# WHEEL-MOTORs.net
KiCad netlist of a schematic drawn in Altium Designer
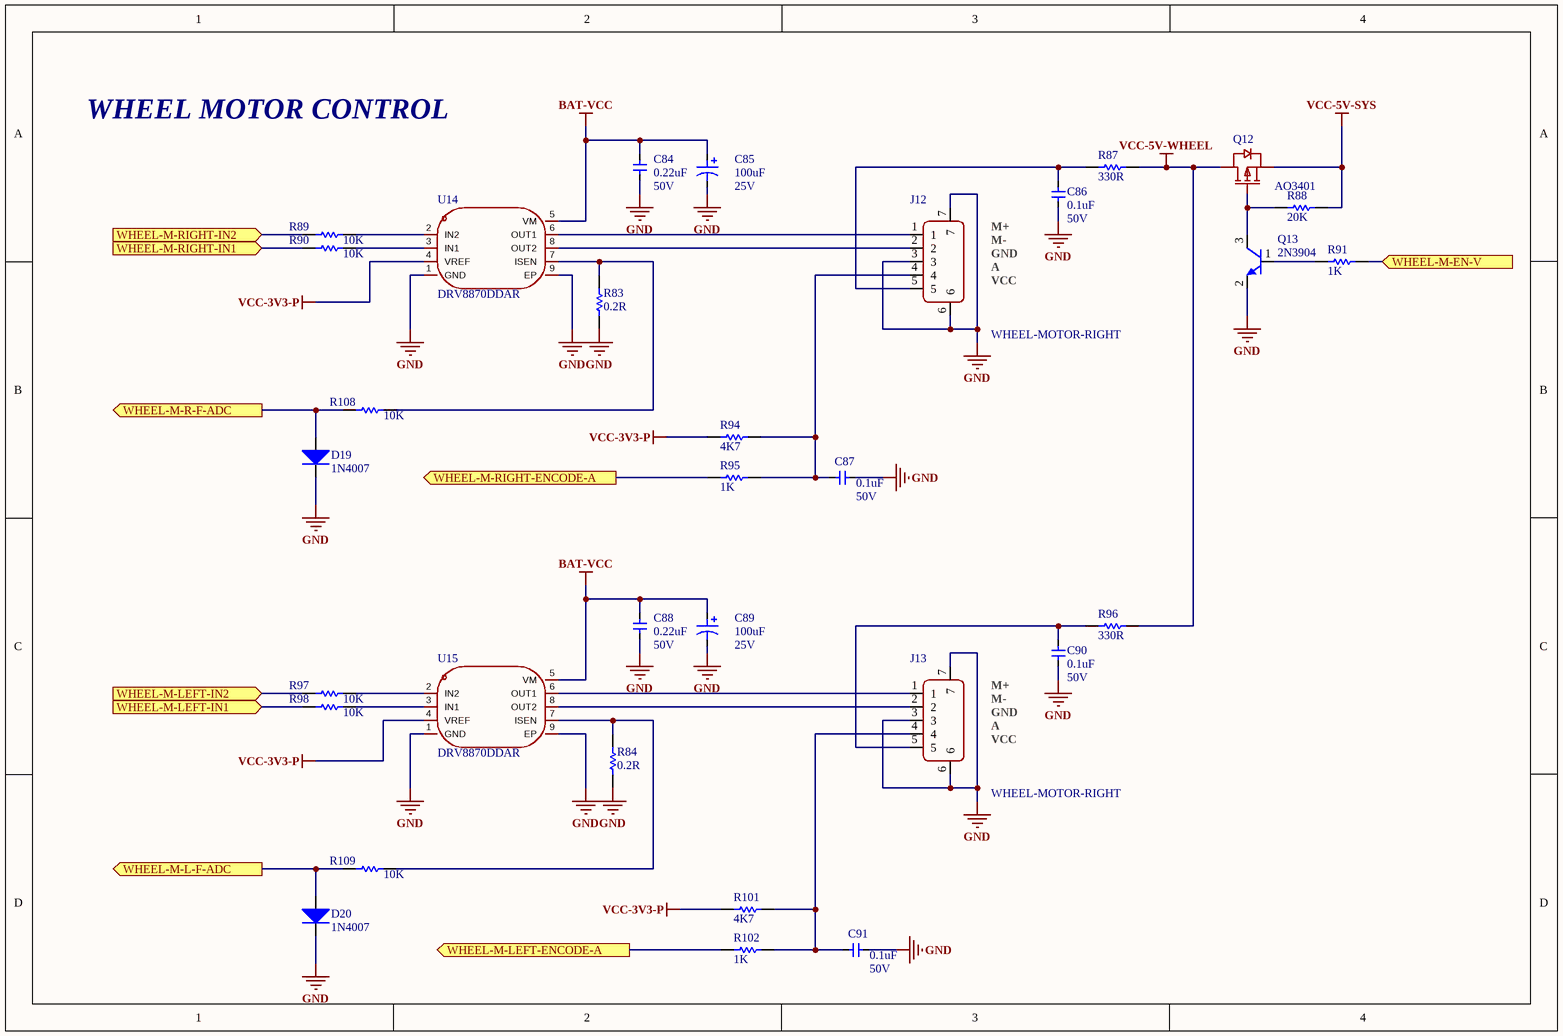
[diagram p0: WHEEL-MOTORs .SchDoc]

(export (version "E")
  (design (tool "Eeschema 10.0.6"))
  (components
    (comp (ref "C84")
      (value "0.22uF")
      (footprint "CAP-0402")
      (fields (field (name "VOLTAGERATE") "50V"))
      (libsource (lib "DesignLibrary") (part "Capacitor-1"))
    )
    (comp (ref "C85")
      (value "100uF")
      (footprint "CAP-SMD_BD6.3-L6.6-W6.6-FD")
      (fields (field (name "VOLTAGERATE") "25V"))
      (libsource (lib "DesignLibrary") (part "Capacitor-2"))
    )
    (comp (ref "C86")
      (value "0.1uF")
      (footprint "CAP-0402")
      (fields (field (name "VOLTAGERATE") "50V"))
      (libsource (lib "DesignLibrary") (part "Capacitor-1"))
    )
    (comp (ref "C87")
      (value "0.1uF")
      (footprint "CAP-0402")
      (fields (field (name "VOLTAGERATE") "50V"))
      (libsource (lib "DesignLibrary") (part "Capacitor-1"))
    )
    (comp (ref "C88")
      (value "0.22uF")
      (footprint "CAP-0402")
      (fields (field (name "VOLTAGERATE") "50V"))
      (libsource (lib "DesignLibrary") (part "Capacitor-1"))
    )
    (comp (ref "C89")
      (value "100uF")
      (footprint "CAP-SMD_BD6.3-L6.6-W6.6-FD")
      (fields (field (name "VOLTAGERATE") "25V"))
      (libsource (lib "DesignLibrary") (part "Capacitor-2"))
    )
    (comp (ref "C90")
      (value "0.1uF")
      (footprint "CAP-0402")
      (fields (field (name "VOLTAGERATE") "50V"))
      (libsource (lib "DesignLibrary") (part "Capacitor-1"))
    )
    (comp (ref "C91")
      (value "0.1uF")
      (footprint "CAP-0402")
      (fields (field (name "VOLTAGERATE") "50V"))
      (libsource (lib "DesignLibrary") (part "Capacitor-1"))
    )
    (comp (ref "D19")
      (value "1N4007")
      (footprint "SOD123")
      (libsource (lib "DesignLibrary") (part "DIODE-1"))
    )
    (comp (ref "D20")
      (value "1N4007")
      (footprint "SOD123")
      (libsource (lib "DesignLibrary") (part "DIODE-1"))
    )
    (comp (ref "J12")
      (value "WHEEL-MOTOR-RIGHT")
      (footprint "CONN-SMD_5P-P1.50_ZX-ZH1.5-5PWT")
      (libsource (lib "DesignLibrary") (part "HDRx5"))
    )
    (comp (ref "J13")
      (value "WHEEL-MOTOR-RIGHT")
      (footprint "CONN-SMD_5P-P1.50_ZX-ZH1.5-5PWT")
      (libsource (lib "DesignLibrary") (part "HDRx5"))
    )
    (comp (ref "Q12")
      (value "AO3401")
      (footprint "SOT23-3D")
      (libsource (lib "DesignLibrary") (part "P-MOS-SOT23"))
    )
    (comp (ref "Q13")
      (value "2N3904")
      (footprint "SOT23-3D")
      (libsource (lib "DesignLibrary") (part "NPN-SOT23"))
    )
    (comp (ref "R83")
      (value "0.2R")
      (footprint "RES-0603")
      (libsource (lib "DesignLibrary") (part "Resistor-1"))
    )
    (comp (ref "R84")
      (value "0.2R")
      (footprint "RES-0603")
      (libsource (lib "DesignLibrary") (part "Resistor-1"))
    )
    (comp (ref "R87")
      (value "330R")
      (footprint "RES-0603")
      (libsource (lib "DesignLibrary") (part "Resistor-1"))
    )
    (comp (ref "R88")
      (value "20K")
      (footprint "RES-0402")
      (libsource (lib "DesignLibrary") (part "Resistor-1"))
    )
    (comp (ref "R89")
      (value "10K")
      (footprint "RES-0402")
      (libsource (lib "DesignLibrary") (part "Resistor-1"))
    )
    (comp (ref "R90")
      (value "10K")
      (footprint "RES-0402")
      (libsource (lib "DesignLibrary") (part "Resistor-1"))
    )
    (comp (ref "R91")
      (value "1K")
      (footprint "RES-0402")
      (libsource (lib "DesignLibrary") (part "Resistor-1"))
    )
    (comp (ref "R94")
      (value "4K7")
      (footprint "RES-0402")
      (libsource (lib "DesignLibrary") (part "Resistor-1"))
    )
    (comp (ref "R95")
      (value "1K")
      (footprint "RES-0402")
      (libsource (lib "DesignLibrary") (part "Resistor-1"))
    )
    (comp (ref "R96")
      (value "330R")
      (footprint "RES-0603")
      (libsource (lib "DesignLibrary") (part "Resistor-1"))
    )
    (comp (ref "R97")
      (value "10K")
      (footprint "RES-0402")
      (libsource (lib "DesignLibrary") (part "Resistor-1"))
    )
    (comp (ref "R98")
      (value "10K")
      (footprint "RES-0402")
      (libsource (lib "DesignLibrary") (part "Resistor-1"))
    )
    (comp (ref "R101")
      (value "4K7")
      (footprint "RES-0402")
      (libsource (lib "DesignLibrary") (part "Resistor-1"))
    )
    (comp (ref "R102")
      (value "1K")
      (footprint "RES-0402")
      (libsource (lib "DesignLibrary") (part "Resistor-1"))
    )
    (comp (ref "R108")
      (value "10K")
      (footprint "RES-0402")
      (libsource (lib "DesignLibrary") (part "Resistor-1"))
    )
    (comp (ref "R109")
      (value "10K")
      (footprint "RES-0402")
      (libsource (lib "DesignLibrary") (part "Resistor-1"))
    )
    (comp (ref "U14")
      (value "DRV8870DDAR")
      (footprint "HSOP-8_L5.0-W4.0-P1.27-LS6.2-BL-EP")
      (libsource (lib "DesignLibrary") (part "DRV8870"))
    )
    (comp (ref "U15")
      (value "DRV8870DDAR")
      (footprint "HSOP-8_L5.0-W4.0-P1.27-LS6.2-BL-EP")
      (libsource (lib "DesignLibrary") (part "DRV8870"))
    )
  )
  (nets
    (net (code "1") (name "/WHEEL-M-EN-V") (class "Default") (node (ref "R91") (pin "2") (pintype "passive")))
    (net (code "2") (name "/WHEEL-M-L-F-ADC") (class "Default")
      (node (ref "D20") (pin "1") (pinfunction "A_1") (pintype "passive"))
      (node (ref "R109") (pin "1") (pintype "passive"))
    )
    (net (code "3") (name "/WHEEL-M-LEFT-ENCODE-A") (class "Default")
      (node (ref "R102") (pin "1") (pintype "passive"))
    )
    (net (code "4") (name "/WHEEL-M-LEFT-IN1") (class "Default")
      (node (ref "R98") (pin "1") (pintype "passive"))
    )
    (net (code "5") (name "/WHEEL-M-LEFT-IN2") (class "Default")
      (node (ref "R97") (pin "1") (pintype "passive"))
    )
    (net (code "6") (name "/WHEEL-M-R-F-ADC") (class "Default")
      (node (ref "D19") (pin "1") (pinfunction "A_1") (pintype "passive"))
      (node (ref "R108") (pin "1") (pintype "passive"))
    )
    (net (code "7") (name "/WHEEL-M-RIGHT-ENCODE-A") (class "Default")
      (node (ref "R95") (pin "1") (pintype "passive"))
    )
    (net (code "8") (name "/WHEEL-M-RIGHT-IN1") (class "Default")
      (node (ref "R90") (pin "1") (pintype "passive"))
    )
    (net (code "9") (name "/WHEEL-M-RIGHT-IN2") (class "Default")
      (node (ref "R89") (pin "1") (pintype "passive"))
    )
    (net (code "10") (name "BAT-VCC") (class "Default")
      (node (ref "C84") (pin "2") (pinfunction "2_2") (pintype "passive"))
      (node (ref "C85") (pin "1") (pinfunction "1_1") (pintype "passive"))
      (node (ref "C88") (pin "2") (pinfunction "2_2") (pintype "passive"))
      (node (ref "C89") (pin "1") (pinfunction "1_1") (pintype "passive"))
      (node (ref "U14") (pin "5") (pinfunction "VM_5") (pintype "passive"))
      (node (ref "U15") (pin "5") (pinfunction "VM_5") (pintype "passive"))
    )
    (net (code "11") (name "GND") (class "Default")
      (node (ref "C84") (pin "1") (pinfunction "1_1") (pintype "passive"))
      (node (ref "C85") (pin "2") (pinfunction "2_2") (pintype "passive"))
      (node (ref "C86") (pin "2") (pinfunction "2_2") (pintype "passive"))
      (node (ref "C87") (pin "1") (pinfunction "1_1") (pintype "passive"))
      (node (ref "C88") (pin "1") (pinfunction "1_1") (pintype "passive"))
      (node (ref "C89") (pin "2") (pinfunction "2_2") (pintype "passive"))
      (node (ref "C90") (pin "2") (pinfunction "2_2") (pintype "passive"))
      (node (ref "C91") (pin "1") (pinfunction "1_1") (pintype "passive"))
      (node (ref "D19") (pin "2") (pinfunction "K_2") (pintype "passive"))
      (node (ref "D20") (pin "2") (pinfunction "K_2") (pintype "passive"))
      (node (ref "J12") (pin "3") (pinfunction "3_3") (pintype "passive"))
      (node (ref "J12") (pin "6") (pinfunction "6_6") (pintype "passive"))
      (node (ref "J12") (pin "7") (pinfunction "7_7") (pintype "passive"))
      (node (ref "J13") (pin "3") (pinfunction "3_3") (pintype "passive"))
      (node (ref "J13") (pin "6") (pinfunction "6_6") (pintype "passive"))
      (node (ref "J13") (pin "7") (pinfunction "7_7") (pintype "passive"))
      (node (ref "Q13") (pin "2") (pinfunction "E_2") (pintype "passive"))
      (node (ref "R83") (pin "1") (pintype "passive"))
      (node (ref "R84") (pin "1") (pintype "passive"))
      (node (ref "U14") (pin "1") (pinfunction "GND_1") (pintype "passive"))
      (node (ref "U14") (pin "9") (pinfunction "EP_9") (pintype "passive"))
      (node (ref "U15") (pin "1") (pinfunction "GND_1") (pintype "passive"))
      (node (ref "U15") (pin "9") (pinfunction "EP_9") (pintype "passive"))
    )
    (net (code "12") (name "Net-(C86-Pad1)") (class "Default")
      (node (ref "C86") (pin "1") (pinfunction "1_1") (pintype "passive"))
      (node (ref "J12") (pin "5") (pinfunction "5_5") (pintype "passive"))
      (node (ref "R87") (pin "1") (pintype "passive"))
    )
    (net (code "13") (name "Net-(C87-Pad2)") (class "Default")
      (node (ref "C87") (pin "2") (pinfunction "2_2") (pintype "passive"))
      (node (ref "J12") (pin "4") (pinfunction "4_4") (pintype "passive"))
      (node (ref "R94") (pin "2") (pintype "passive"))
      (node (ref "R95") (pin "2") (pintype "passive"))
    )
    (net (code "14") (name "Net-(C90-Pad1)") (class "Default")
      (node (ref "C90") (pin "1") (pinfunction "1_1") (pintype "passive"))
      (node (ref "J13") (pin "5") (pinfunction "5_5") (pintype "passive"))
      (node (ref "R96") (pin "1") (pintype "passive"))
    )
    (net (code "15") (name "Net-(C91-Pad2)") (class "Default")
      (node (ref "C91") (pin "2") (pinfunction "2_2") (pintype "passive"))
      (node (ref "J13") (pin "4") (pinfunction "4_4") (pintype "passive"))
      (node (ref "R101") (pin "2") (pintype "passive"))
      (node (ref "R102") (pin "2") (pintype "passive"))
    )
    (net (code "16") (name "Net-(Q12-G)") (class "Default")
      (node (ref "Q12") (pin "1") (pinfunction "G_1") (pintype "passive"))
      (node (ref "Q13") (pin "3") (pinfunction "C_3") (pintype "passive"))
      (node (ref "R88") (pin "1") (pintype "passive"))
    )
    (net (code "17") (name "Net-(Q13-B)") (class "Default")
      (node (ref "Q13") (pin "1") (pinfunction "B_1") (pintype "passive"))
      (node (ref "R91") (pin "1") (pintype "passive"))
    )
    (net (code "18") (name "Net-(U14-IN1)") (class "Default")
      (node (ref "R90") (pin "2") (pintype "passive"))
      (node (ref "U14") (pin "3") (pinfunction "IN1_3") (pintype "passive"))
    )
    (net (code "19") (name "Net-(U14-IN2)") (class "Default")
      (node (ref "R89") (pin "2") (pintype "passive"))
      (node (ref "U14") (pin "2") (pinfunction "IN2_2") (pintype "passive"))
    )
    (net (code "20") (name "Net-(U14-ISEN)") (class "Default")
      (node (ref "R108") (pin "2") (pintype "passive"))
      (node (ref "R83") (pin "2") (pintype "passive"))
      (node (ref "U14") (pin "7") (pinfunction "ISEN_7") (pintype "passive"))
    )
    (net (code "21") (name "Net-(U14-OUT1)") (class "Default")
      (node (ref "J12") (pin "1") (pinfunction "1_1") (pintype "passive"))
      (node (ref "U14") (pin "6") (pinfunction "OUT1_6") (pintype "passive"))
    )
    (net (code "22") (name "Net-(U14-OUT2)") (class "Default")
      (node (ref "J12") (pin "2") (pinfunction "2_2") (pintype "passive"))
      (node (ref "U14") (pin "8") (pinfunction "OUT2_8") (pintype "passive"))
    )
    (net (code "23") (name "Net-(U15-IN1)") (class "Default")
      (node (ref "R98") (pin "2") (pintype "passive"))
      (node (ref "U15") (pin "3") (pinfunction "IN1_3") (pintype "passive"))
    )
    (net (code "24") (name "Net-(U15-IN2)") (class "Default")
      (node (ref "R97") (pin "2") (pintype "passive"))
      (node (ref "U15") (pin "2") (pinfunction "IN2_2") (pintype "passive"))
    )
    (net (code "25") (name "Net-(U15-ISEN)") (class "Default")
      (node (ref "R109") (pin "2") (pintype "passive"))
      (node (ref "R84") (pin "2") (pintype "passive"))
      (node (ref "U15") (pin "7") (pinfunction "ISEN_7") (pintype "passive"))
    )
    (net (code "26") (name "Net-(U15-OUT1)") (class "Default")
      (node (ref "J13") (pin "1") (pinfunction "1_1") (pintype "passive"))
      (node (ref "U15") (pin "6") (pinfunction "OUT1_6") (pintype "passive"))
    )
    (net (code "27") (name "Net-(U15-OUT2)") (class "Default")
      (node (ref "J13") (pin "2") (pinfunction "2_2") (pintype "passive"))
      (node (ref "U15") (pin "8") (pinfunction "OUT2_8") (pintype "passive"))
    )
    (net (code "28") (name "VCC-3V3-P") (class "Default")
      (node (ref "R101") (pin "1") (pintype "passive"))
      (node (ref "R94") (pin "1") (pintype "passive"))
      (node (ref "U14") (pin "4") (pinfunction "VREF_4") (pintype "passive"))
      (node (ref "U15") (pin "4") (pinfunction "VREF_4") (pintype "passive"))
    )
    (net (code "29") (name "VCC-5V-SYS") (class "Default")
      (node (ref "Q12") (pin "2") (pinfunction "S_2") (pintype "passive"))
      (node (ref "R88") (pin "2") (pintype "passive"))
    )
    (net (code "30") (name "VCC-5V-WHEEL") (class "Default")
      (node (ref "Q12") (pin "3") (pinfunction "D_3") (pintype "passive"))
      (node (ref "R87") (pin "2") (pintype "passive"))
      (node (ref "R96") (pin "2") (pintype "passive"))
    )
  )
)
